# EBF6ULL_F1____AD.net
KiCad netlist of a schematic drawn in Altium Designer
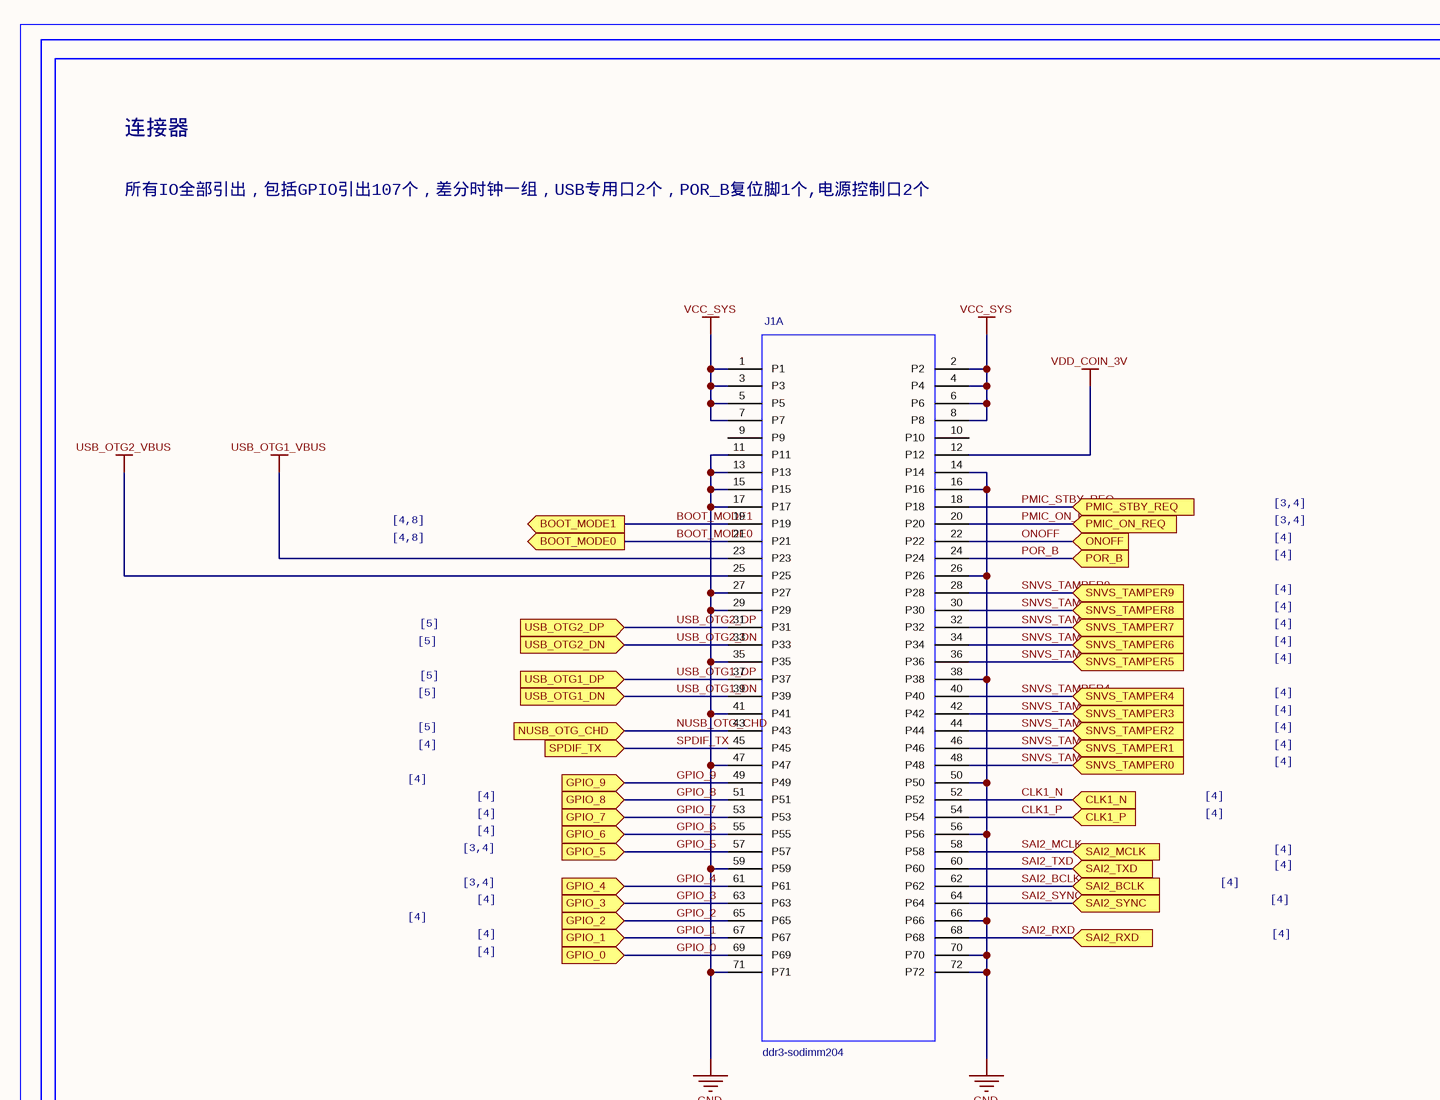
[diagram p0: 野火_EBF6ULL F1 核心板_原理图封装参考设计_AD格式.SchDoc, top left]
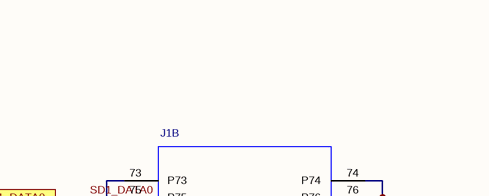
[diagram p1: 野火_EBF6ULL F1 核心板_原理图封装参考设计_AD格式.SchDoc, top right]
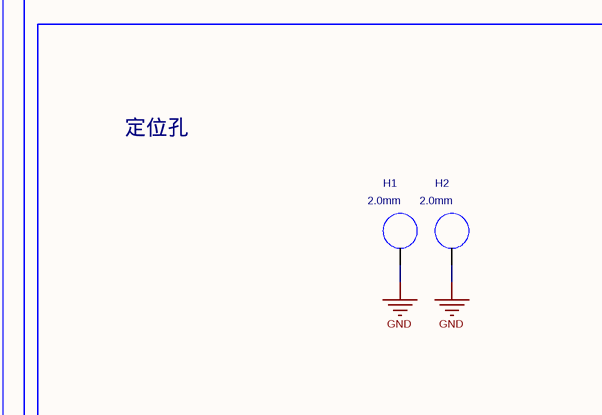
[diagram p2: 野火_EBF6ULL F1 核心板_原理图封装参考设计_AD格式.SchDoc, bottom left]
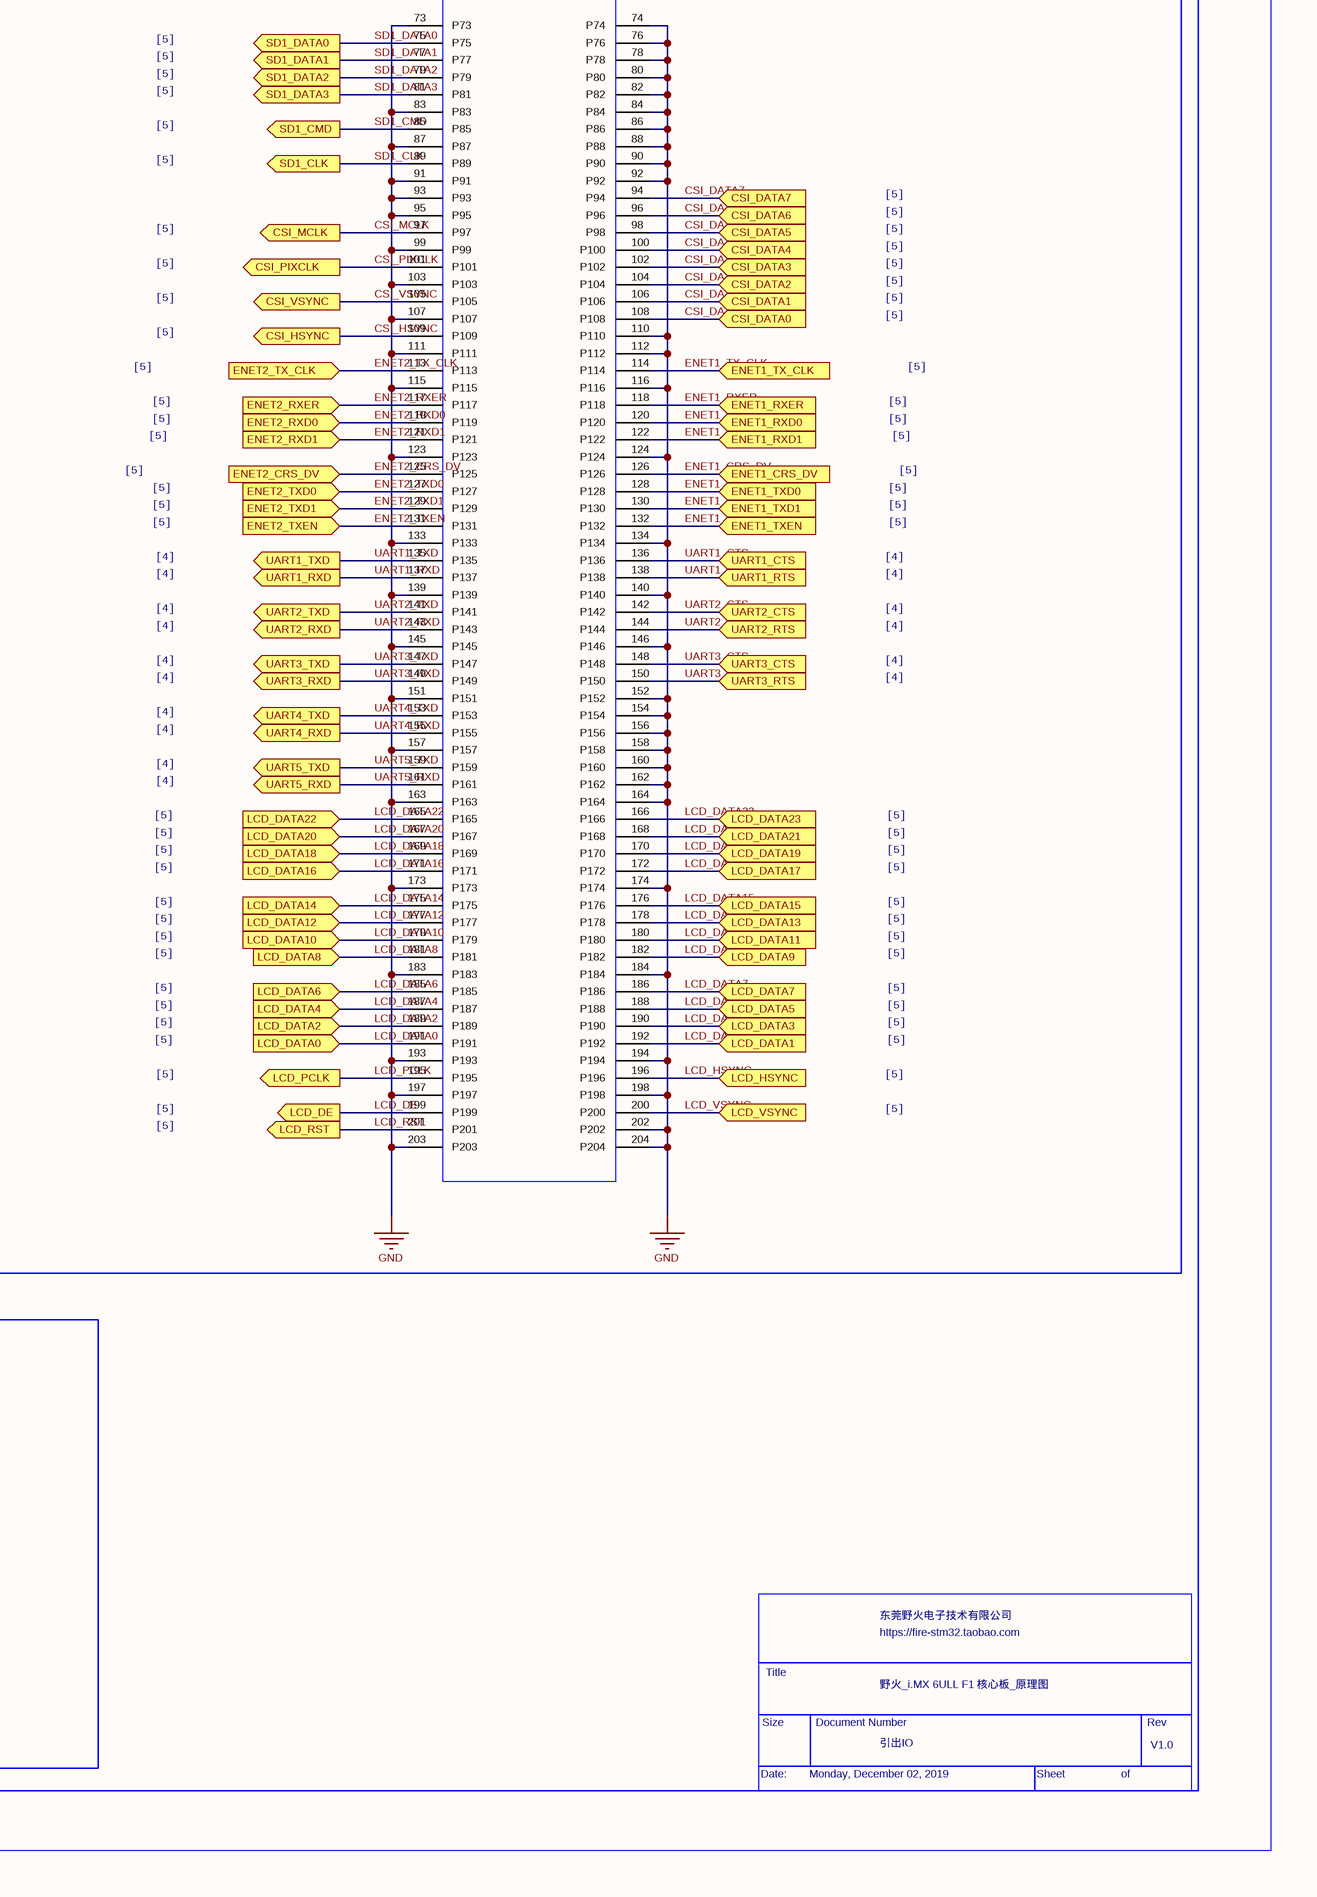
[diagram p3: 野火_EBF6ULL F1 核心板_原理图封装参考设计_AD格式.SchDoc, bottom right]

(export (version "E")
  (design (tool "Eeschema 10.0.6"))
  (components
    (comp (ref "H1")
      (value "2.0mm")
      (footprint "T2_5-4")
      (description "FASTENER, STANDOFF 4.5MMX3.53XM3.0X0.5 ROUND THR .635\"L BRASS")
      (fields (field (name "Comment") "SPACER_0"))
      (libsource (lib "*") (part "SPACER_0"))
    )
    (comp (ref "H2")
      (value "2.0mm")
      (footprint "T2_5-4")
      (description "FASTENER, STANDOFF 4.5MMX3.53XM3.0X0.5 ROUND THR .635\"L BRASS")
      (fields (field (name "Comment") "SPACER_0"))
      (libsource (lib "*") (part "SPACER_0"))
    )
    (comp (ref "J1")
      (value "ddr3-sodimm204")
      (footprint "DDR3-SODIMM204-GOLD_FINGER")
      (fields (field (name "Comment") "DDR3-SODIMM204"))
      (libsource (lib "*") (part "DDR3-SODIMM204"))
    )
  )
  (nets
    (net (code "1") (name "/BOOT_MODE0") (class "Default")
      (node (ref "J1") (pin "21") (pinfunction "P21_21") (pintype "passive"))
    )
    (net (code "2") (name "/BOOT_MODE1") (class "Default")
      (node (ref "J1") (pin "19") (pinfunction "P19_19") (pintype "passive"))
    )
    (net (code "3") (name "/CLK1_N") (class "Default")
      (node (ref "J1") (pin "52") (pinfunction "P52_52") (pintype "passive"))
    )
    (net (code "4") (name "/CLK1_P") (class "Default")
      (node (ref "J1") (pin "54") (pinfunction "P54_54") (pintype "passive"))
    )
    (net (code "5") (name "/CSI_DATA0") (class "Default")
      (node (ref "J1") (pin "108") (pinfunction "P108_108") (pintype "passive"))
    )
    (net (code "6") (name "/CSI_DATA1") (class "Default")
      (node (ref "J1") (pin "106") (pinfunction "P106_106") (pintype "passive"))
    )
    (net (code "7") (name "/CSI_DATA2") (class "Default")
      (node (ref "J1") (pin "104") (pinfunction "P104_104") (pintype "passive"))
    )
    (net (code "8") (name "/CSI_DATA3") (class "Default")
      (node (ref "J1") (pin "102") (pinfunction "P102_102") (pintype "passive"))
    )
    (net (code "9") (name "/CSI_DATA4") (class "Default")
      (node (ref "J1") (pin "100") (pinfunction "P100_100") (pintype "passive"))
    )
    (net (code "10") (name "/CSI_DATA5") (class "Default")
      (node (ref "J1") (pin "98") (pinfunction "P98_98") (pintype "passive"))
    )
    (net (code "11") (name "/CSI_DATA6") (class "Default")
      (node (ref "J1") (pin "96") (pinfunction "P96_96") (pintype "passive"))
    )
    (net (code "12") (name "/CSI_DATA7") (class "Default")
      (node (ref "J1") (pin "94") (pinfunction "P94_94") (pintype "passive"))
    )
    (net (code "13") (name "/CSI_HSYNC") (class "Default")
      (node (ref "J1") (pin "109") (pinfunction "P109_109") (pintype "passive"))
    )
    (net (code "14") (name "/CSI_MCLK") (class "Default")
      (node (ref "J1") (pin "97") (pinfunction "P97_97") (pintype "passive"))
    )
    (net (code "15") (name "/CSI_PIXCLK") (class "Default")
      (node (ref "J1") (pin "101") (pinfunction "P101_101") (pintype "passive"))
    )
    (net (code "16") (name "/CSI_VSYNC") (class "Default")
      (node (ref "J1") (pin "105") (pinfunction "P105_105") (pintype "passive"))
    )
    (net (code "17") (name "/ENET1_CRS_DV") (class "Default")
      (node (ref "J1") (pin "126") (pinfunction "P126_126") (pintype "passive"))
    )
    (net (code "18") (name "/ENET1_RXD0") (class "Default")
      (node (ref "J1") (pin "120") (pinfunction "P120_120") (pintype "passive"))
    )
    (net (code "19") (name "/ENET1_RXD1") (class "Default")
      (node (ref "J1") (pin "122") (pinfunction "P122_122") (pintype "passive"))
    )
    (net (code "20") (name "/ENET1_RXER") (class "Default")
      (node (ref "J1") (pin "118") (pinfunction "P118_118") (pintype "passive"))
    )
    (net (code "21") (name "/ENET1_TXD0") (class "Default")
      (node (ref "J1") (pin "128") (pinfunction "P128_128") (pintype "passive"))
    )
    (net (code "22") (name "/ENET1_TXD1") (class "Default")
      (node (ref "J1") (pin "130") (pinfunction "P130_130") (pintype "passive"))
    )
    (net (code "23") (name "/ENET1_TXEN") (class "Default")
      (node (ref "J1") (pin "132") (pinfunction "P132_132") (pintype "passive"))
    )
    (net (code "24") (name "/ENET1_TX_CLK") (class "Default")
      (node (ref "J1") (pin "114") (pinfunction "P114_114") (pintype "passive"))
    )
    (net (code "25") (name "/ENET2_CRS_DV") (class "Default")
      (node (ref "J1") (pin "125") (pinfunction "P125_125") (pintype "passive"))
    )
    (net (code "26") (name "/ENET2_RXD0") (class "Default")
      (node (ref "J1") (pin "119") (pinfunction "P119_119") (pintype "passive"))
    )
    (net (code "27") (name "/ENET2_RXD1") (class "Default")
      (node (ref "J1") (pin "121") (pinfunction "P121_121") (pintype "passive"))
    )
    (net (code "28") (name "/ENET2_RXER") (class "Default")
      (node (ref "J1") (pin "117") (pinfunction "P117_117") (pintype "passive"))
    )
    (net (code "29") (name "/ENET2_TXD0") (class "Default")
      (node (ref "J1") (pin "127") (pinfunction "P127_127") (pintype "passive"))
    )
    (net (code "30") (name "/ENET2_TXD1") (class "Default")
      (node (ref "J1") (pin "129") (pinfunction "P129_129") (pintype "passive"))
    )
    (net (code "31") (name "/ENET2_TXEN") (class "Default")
      (node (ref "J1") (pin "131") (pinfunction "P131_131") (pintype "passive"))
    )
    (net (code "32") (name "/ENET2_TX_CLK") (class "Default")
      (node (ref "J1") (pin "113") (pinfunction "P113_113") (pintype "passive"))
    )
    (net (code "33") (name "/GPIO_0") (class "Default")
      (node (ref "J1") (pin "69") (pinfunction "P69_69") (pintype "passive"))
    )
    (net (code "34") (name "/GPIO_1") (class "Default")
      (node (ref "J1") (pin "67") (pinfunction "P67_67") (pintype "passive"))
    )
    (net (code "35") (name "/GPIO_2") (class "Default")
      (node (ref "J1") (pin "65") (pinfunction "P65_65") (pintype "passive"))
    )
    (net (code "36") (name "/GPIO_3") (class "Default")
      (node (ref "J1") (pin "63") (pinfunction "P63_63") (pintype "passive"))
    )
    (net (code "37") (name "/GPIO_4") (class "Default")
      (node (ref "J1") (pin "61") (pinfunction "P61_61") (pintype "passive"))
    )
    (net (code "38") (name "/GPIO_5") (class "Default")
      (node (ref "J1") (pin "57") (pinfunction "P57_57") (pintype "passive"))
    )
    (net (code "39") (name "/GPIO_6") (class "Default")
      (node (ref "J1") (pin "55") (pinfunction "P55_55") (pintype "passive"))
    )
    (net (code "40") (name "/GPIO_7") (class "Default")
      (node (ref "J1") (pin "53") (pinfunction "P53_53") (pintype "passive"))
    )
    (net (code "41") (name "/GPIO_8") (class "Default")
      (node (ref "J1") (pin "51") (pinfunction "P51_51") (pintype "passive"))
    )
    (net (code "42") (name "/GPIO_9") (class "Default")
      (node (ref "J1") (pin "49") (pinfunction "P49_49") (pintype "passive"))
    )
    (net (code "43") (name "/LCD_DATA0") (class "Default")
      (node (ref "J1") (pin "191") (pinfunction "P191_191") (pintype "passive"))
    )
    (net (code "44") (name "/LCD_DATA1") (class "Default")
      (node (ref "J1") (pin "192") (pinfunction "P192_192") (pintype "passive"))
    )
    (net (code "45") (name "/LCD_DATA2") (class "Default")
      (node (ref "J1") (pin "189") (pinfunction "P189_189") (pintype "passive"))
    )
    (net (code "46") (name "/LCD_DATA3") (class "Default")
      (node (ref "J1") (pin "190") (pinfunction "P190_190") (pintype "passive"))
    )
    (net (code "47") (name "/LCD_DATA4") (class "Default")
      (node (ref "J1") (pin "187") (pinfunction "P187_187") (pintype "passive"))
    )
    (net (code "48") (name "/LCD_DATA5") (class "Default")
      (node (ref "J1") (pin "188") (pinfunction "P188_188") (pintype "passive"))
    )
    (net (code "49") (name "/LCD_DATA6") (class "Default")
      (node (ref "J1") (pin "185") (pinfunction "P185_185") (pintype "passive"))
    )
    (net (code "50") (name "/LCD_DATA7") (class "Default")
      (node (ref "J1") (pin "186") (pinfunction "P186_186") (pintype "passive"))
    )
    (net (code "51") (name "/LCD_DATA8") (class "Default")
      (node (ref "J1") (pin "181") (pinfunction "P181_181") (pintype "passive"))
    )
    (net (code "52") (name "/LCD_DATA9") (class "Default")
      (node (ref "J1") (pin "182") (pinfunction "P182_182") (pintype "passive"))
    )
    (net (code "53") (name "/LCD_DATA10") (class "Default")
      (node (ref "J1") (pin "179") (pinfunction "P179_179") (pintype "passive"))
    )
    (net (code "54") (name "/LCD_DATA11") (class "Default")
      (node (ref "J1") (pin "180") (pinfunction "P180_180") (pintype "passive"))
    )
    (net (code "55") (name "/LCD_DATA12") (class "Default")
      (node (ref "J1") (pin "177") (pinfunction "P177_177") (pintype "passive"))
    )
    (net (code "56") (name "/LCD_DATA13") (class "Default")
      (node (ref "J1") (pin "178") (pinfunction "P178_178") (pintype "passive"))
    )
    (net (code "57") (name "/LCD_DATA14") (class "Default")
      (node (ref "J1") (pin "175") (pinfunction "P175_175") (pintype "passive"))
    )
    (net (code "58") (name "/LCD_DATA15") (class "Default")
      (node (ref "J1") (pin "176") (pinfunction "P176_176") (pintype "passive"))
    )
    (net (code "59") (name "/LCD_DATA16") (class "Default")
      (node (ref "J1") (pin "171") (pinfunction "P171_171") (pintype "passive"))
    )
    (net (code "60") (name "/LCD_DATA17") (class "Default")
      (node (ref "J1") (pin "172") (pinfunction "P172_172") (pintype "passive"))
    )
    (net (code "61") (name "/LCD_DATA18") (class "Default")
      (node (ref "J1") (pin "169") (pinfunction "P169_169") (pintype "passive"))
    )
    (net (code "62") (name "/LCD_DATA19") (class "Default")
      (node (ref "J1") (pin "170") (pinfunction "P170_170") (pintype "passive"))
    )
    (net (code "63") (name "/LCD_DATA20") (class "Default")
      (node (ref "J1") (pin "167") (pinfunction "P167_167") (pintype "passive"))
    )
    (net (code "64") (name "/LCD_DATA21") (class "Default")
      (node (ref "J1") (pin "168") (pinfunction "P168_168") (pintype "passive"))
    )
    (net (code "65") (name "/LCD_DATA22") (class "Default")
      (node (ref "J1") (pin "165") (pinfunction "P165_165") (pintype "passive"))
    )
    (net (code "66") (name "/LCD_DATA23") (class "Default")
      (node (ref "J1") (pin "166") (pinfunction "P166_166") (pintype "passive"))
    )
    (net (code "67") (name "/LCD_DE") (class "Default")
      (node (ref "J1") (pin "199") (pinfunction "P199_199") (pintype "passive"))
    )
    (net (code "68") (name "/LCD_HSYNC") (class "Default")
      (node (ref "J1") (pin "196") (pinfunction "P196_196") (pintype "passive"))
    )
    (net (code "69") (name "/LCD_PCLK") (class "Default")
      (node (ref "J1") (pin "195") (pinfunction "P195_195") (pintype "passive"))
    )
    (net (code "70") (name "/LCD_RST") (class "Default")
      (node (ref "J1") (pin "201") (pinfunction "P201_201") (pintype "passive"))
    )
    (net (code "71") (name "/LCD_VSYNC") (class "Default")
      (node (ref "J1") (pin "200") (pinfunction "P200_200") (pintype "passive"))
    )
    (net (code "72") (name "/NUSB_OTG_CHD") (class "Default")
      (node (ref "J1") (pin "43") (pinfunction "P43_43") (pintype "passive"))
    )
    (net (code "73") (name "/ONOFF") (class "Default")
      (node (ref "J1") (pin "22") (pinfunction "P22_22") (pintype "passive"))
    )
    (net (code "74") (name "/PMIC_ON_REQ") (class "Default")
      (node (ref "J1") (pin "20") (pinfunction "P20_20") (pintype "passive"))
    )
    (net (code "75") (name "/PMIC_STBY_REQ") (class "Default")
      (node (ref "J1") (pin "18") (pinfunction "P18_18") (pintype "passive"))
    )
    (net (code "76") (name "/POR_B") (class "Default")
      (node (ref "J1") (pin "24") (pinfunction "P24_24") (pintype "passive"))
    )
    (net (code "77") (name "/SAI2_BCLK") (class "Default")
      (node (ref "J1") (pin "62") (pinfunction "P62_62") (pintype "passive"))
    )
    (net (code "78") (name "/SAI2_MCLK") (class "Default")
      (node (ref "J1") (pin "58") (pinfunction "P58_58") (pintype "passive"))
    )
    (net (code "79") (name "/SAI2_RXD") (class "Default")
      (node (ref "J1") (pin "68") (pinfunction "P68_68") (pintype "passive"))
    )
    (net (code "80") (name "/SAI2_SYNC") (class "Default")
      (node (ref "J1") (pin "64") (pinfunction "P64_64") (pintype "passive"))
    )
    (net (code "81") (name "/SAI2_TXD") (class "Default")
      (node (ref "J1") (pin "60") (pinfunction "P60_60") (pintype "passive"))
    )
    (net (code "82") (name "/SD1_CLK") (class "Default")
      (node (ref "J1") (pin "89") (pinfunction "P89_89") (pintype "passive"))
    )
    (net (code "83") (name "/SD1_CMD") (class "Default")
      (node (ref "J1") (pin "85") (pinfunction "P85_85") (pintype "passive"))
    )
    (net (code "84") (name "/SD1_DATA0") (class "Default")
      (node (ref "J1") (pin "75") (pinfunction "P75_75") (pintype "passive"))
    )
    (net (code "85") (name "/SD1_DATA1") (class "Default")
      (node (ref "J1") (pin "77") (pinfunction "P77_77") (pintype "passive"))
    )
    (net (code "86") (name "/SD1_DATA2") (class "Default")
      (node (ref "J1") (pin "79") (pinfunction "P79_79") (pintype "passive"))
    )
    (net (code "87") (name "/SD1_DATA3") (class "Default")
      (node (ref "J1") (pin "81") (pinfunction "P81_81") (pintype "passive"))
    )
    (net (code "88") (name "/SNVS_TAMPER0") (class "Default")
      (node (ref "J1") (pin "48") (pinfunction "P48_48") (pintype "passive"))
    )
    (net (code "89") (name "/SNVS_TAMPER1") (class "Default")
      (node (ref "J1") (pin "46") (pinfunction "P46_46") (pintype "passive"))
    )
    (net (code "90") (name "/SNVS_TAMPER2") (class "Default")
      (node (ref "J1") (pin "44") (pinfunction "P44_44") (pintype "passive"))
    )
    (net (code "91") (name "/SNVS_TAMPER3") (class "Default")
      (node (ref "J1") (pin "42") (pinfunction "P42_42") (pintype "passive"))
    )
    (net (code "92") (name "/SNVS_TAMPER4") (class "Default")
      (node (ref "J1") (pin "40") (pinfunction "P40_40") (pintype "passive"))
    )
    (net (code "93") (name "/SNVS_TAMPER5") (class "Default")
      (node (ref "J1") (pin "36") (pinfunction "P36_36") (pintype "passive"))
    )
    (net (code "94") (name "/SNVS_TAMPER6") (class "Default")
      (node (ref "J1") (pin "34") (pinfunction "P34_34") (pintype "passive"))
    )
    (net (code "95") (name "/SNVS_TAMPER7") (class "Default")
      (node (ref "J1") (pin "32") (pinfunction "P32_32") (pintype "passive"))
    )
    (net (code "96") (name "/SNVS_TAMPER8") (class "Default")
      (node (ref "J1") (pin "30") (pinfunction "P30_30") (pintype "passive"))
    )
    (net (code "97") (name "/SNVS_TAMPER9") (class "Default")
      (node (ref "J1") (pin "28") (pinfunction "P28_28") (pintype "passive"))
    )
    (net (code "98") (name "/SPDIF_TX") (class "Default")
      (node (ref "J1") (pin "45") (pinfunction "P45_45") (pintype "passive"))
    )
    (net (code "99") (name "/UART1_CTS") (class "Default")
      (node (ref "J1") (pin "136") (pinfunction "P136_136") (pintype "passive"))
    )
    (net (code "100") (name "/UART1_RTS") (class "Default")
      (node (ref "J1") (pin "138") (pinfunction "P138_138") (pintype "passive"))
    )
    (net (code "101") (name "/UART1_RXD") (class "Default")
      (node (ref "J1") (pin "137") (pinfunction "P137_137") (pintype "passive"))
    )
    (net (code "102") (name "/UART1_TXD") (class "Default")
      (node (ref "J1") (pin "135") (pinfunction "P135_135") (pintype "passive"))
    )
    (net (code "103") (name "/UART2_CTS") (class "Default")
      (node (ref "J1") (pin "142") (pinfunction "P142_142") (pintype "passive"))
    )
    (net (code "104") (name "/UART2_RTS") (class "Default")
      (node (ref "J1") (pin "144") (pinfunction "P144_144") (pintype "passive"))
    )
    (net (code "105") (name "/UART2_RXD") (class "Default")
      (node (ref "J1") (pin "143") (pinfunction "P143_143") (pintype "passive"))
    )
    (net (code "106") (name "/UART2_TXD") (class "Default")
      (node (ref "J1") (pin "141") (pinfunction "P141_141") (pintype "passive"))
    )
    (net (code "107") (name "/UART3_CTS") (class "Default")
      (node (ref "J1") (pin "148") (pinfunction "P148_148") (pintype "passive"))
    )
    (net (code "108") (name "/UART3_RTS") (class "Default")
      (node (ref "J1") (pin "150") (pinfunction "P150_150") (pintype "passive"))
    )
    (net (code "109") (name "/UART3_RXD") (class "Default")
      (node (ref "J1") (pin "149") (pinfunction "P149_149") (pintype "passive"))
    )
    (net (code "110") (name "/UART3_TXD") (class "Default")
      (node (ref "J1") (pin "147") (pinfunction "P147_147") (pintype "passive"))
    )
    (net (code "111") (name "/UART4_RXD") (class "Default")
      (node (ref "J1") (pin "155") (pinfunction "P155_155") (pintype "passive"))
    )
    (net (code "112") (name "/UART4_TXD") (class "Default")
      (node (ref "J1") (pin "153") (pinfunction "P153_153") (pintype "passive"))
    )
    (net (code "113") (name "/UART5_RXD") (class "Default")
      (node (ref "J1") (pin "161") (pinfunction "P161_161") (pintype "passive"))
    )
    (net (code "114") (name "/UART5_TXD") (class "Default")
      (node (ref "J1") (pin "159") (pinfunction "P159_159") (pintype "passive"))
    )
    (net (code "115") (name "/USB_OTG1_DN") (class "Default")
      (node (ref "J1") (pin "39") (pinfunction "P39_39") (pintype "passive"))
    )
    (net (code "116") (name "/USB_OTG1_DP") (class "Default")
      (node (ref "J1") (pin "37") (pinfunction "P37_37") (pintype "passive"))
    )
    (net (code "117") (name "/USB_OTG2_DN") (class "Default")
      (node (ref "J1") (pin "33") (pinfunction "P33_33") (pintype "passive"))
    )
    (net (code "118") (name "/USB_OTG2_DP") (class "Default")
      (node (ref "J1") (pin "31") (pinfunction "P31_31") (pintype "passive"))
    )
    (net (code "119") (name "GND") (class "Default")
      (node (ref "H1") (pin "1") (pinfunction "NC_1_1") (pintype "passive"))
      (node (ref "H2") (pin "1") (pinfunction "NC_1_1") (pintype "passive"))
      (node (ref "J1") (pin "103") (pinfunction "P103_103") (pintype "passive"))
      (node (ref "J1") (pin "107") (pinfunction "P107_107") (pintype "passive"))
      (node (ref "J1") (pin "11") (pinfunction "P11_11") (pintype "passive"))
      (node (ref "J1") (pin "110") (pinfunction "P110_110") (pintype "passive"))
      (node (ref "J1") (pin "111") (pinfunction "P111_111") (pintype "passive"))
      (node (ref "J1") (pin "112") (pinfunction "P112_112") (pintype "passive"))
      (node (ref "J1") (pin "115") (pinfunction "P115_115") (pintype "passive"))
      (node (ref "J1") (pin "116") (pinfunction "P116_116") (pintype "passive"))
      (node (ref "J1") (pin "123") (pinfunction "P123_123") (pintype "passive"))
      (node (ref "J1") (pin "124") (pinfunction "P124_124") (pintype "passive"))
      (node (ref "J1") (pin "13") (pinfunction "P13_13") (pintype "passive"))
      (node (ref "J1") (pin "133") (pinfunction "P133_133") (pintype "passive"))
      (node (ref "J1") (pin "134") (pinfunction "P134_134") (pintype "passive"))
      (node (ref "J1") (pin "139") (pinfunction "P139_139") (pintype "passive"))
      (node (ref "J1") (pin "14") (pinfunction "P14_14") (pintype "passive"))
      (node (ref "J1") (pin "140") (pinfunction "P140_140") (pintype "passive"))
      (node (ref "J1") (pin "145") (pinfunction "P145_145") (pintype "passive"))
      (node (ref "J1") (pin "146") (pinfunction "P146_146") (pintype "passive"))
      (node (ref "J1") (pin "15") (pinfunction "P15_15") (pintype "passive"))
      (node (ref "J1") (pin "151") (pinfunction "P151_151") (pintype "passive"))
      (node (ref "J1") (pin "152") (pinfunction "P152_152") (pintype "passive"))
      (node (ref "J1") (pin "154") (pinfunction "P154_154") (pintype "passive"))
      (node (ref "J1") (pin "156") (pinfunction "P156_156") (pintype "passive"))
      (node (ref "J1") (pin "157") (pinfunction "P157_157") (pintype "passive"))
      (node (ref "J1") (pin "158") (pinfunction "P158_158") (pintype "passive"))
      (node (ref "J1") (pin "16") (pinfunction "P16_16") (pintype "passive"))
      (node (ref "J1") (pin "160") (pinfunction "P160_160") (pintype "passive"))
      (node (ref "J1") (pin "162") (pinfunction "P162_162") (pintype "passive"))
      (node (ref "J1") (pin "163") (pinfunction "P163_163") (pintype "passive"))
      (node (ref "J1") (pin "164") (pinfunction "P164_164") (pintype "passive"))
      (node (ref "J1") (pin "17") (pinfunction "P17_17") (pintype "passive"))
      (node (ref "J1") (pin "173") (pinfunction "P173_173") (pintype "passive"))
      (node (ref "J1") (pin "174") (pinfunction "P174_174") (pintype "passive"))
      (node (ref "J1") (pin "183") (pinfunction "P183_183") (pintype "passive"))
      (node (ref "J1") (pin "184") (pinfunction "P184_184") (pintype "passive"))
      (node (ref "J1") (pin "193") (pinfunction "P193_193") (pintype "passive"))
      (node (ref "J1") (pin "194") (pinfunction "P194_194") (pintype "passive"))
      (node (ref "J1") (pin "197") (pinfunction "P197_197") (pintype "passive"))
      (node (ref "J1") (pin "198") (pinfunction "P198_198") (pintype "passive"))
      (node (ref "J1") (pin "202") (pinfunction "P202_202") (pintype "passive"))
      (node (ref "J1") (pin "203") (pinfunction "P203_203") (pintype "passive"))
      (node (ref "J1") (pin "204") (pinfunction "P204_204") (pintype "passive"))
      (node (ref "J1") (pin "26") (pinfunction "P26_26") (pintype "passive"))
      (node (ref "J1") (pin "27") (pinfunction "P27_27") (pintype "passive"))
      (node (ref "J1") (pin "29") (pinfunction "P29_29") (pintype "passive"))
      (node (ref "J1") (pin "35") (pinfunction "P35_35") (pintype "passive"))
      (node (ref "J1") (pin "38") (pinfunction "P38_38") (pintype "passive"))
      (node (ref "J1") (pin "41") (pinfunction "P41_41") (pintype "passive"))
      (node (ref "J1") (pin "47") (pinfunction "P47_47") (pintype "passive"))
      (node (ref "J1") (pin "50") (pinfunction "P50_50") (pintype "passive"))
      (node (ref "J1") (pin "56") (pinfunction "P56_56") (pintype "passive"))
      (node (ref "J1") (pin "59") (pinfunction "P59_59") (pintype "passive"))
      (node (ref "J1") (pin "66") (pinfunction "P66_66") (pintype "passive"))
      (node (ref "J1") (pin "70") (pinfunction "P70_70") (pintype "passive"))
      (node (ref "J1") (pin "71") (pinfunction "P71_71") (pintype "passive"))
      (node (ref "J1") (pin "72") (pinfunction "P72_72") (pintype "passive"))
      (node (ref "J1") (pin "73") (pinfunction "P73_73") (pintype "passive"))
      (node (ref "J1") (pin "74") (pinfunction "P74_74") (pintype "passive"))
      (node (ref "J1") (pin "76") (pinfunction "P76_76") (pintype "passive"))
      (node (ref "J1") (pin "78") (pinfunction "P78_78") (pintype "passive"))
      (node (ref "J1") (pin "80") (pinfunction "P80_80") (pintype "passive"))
      (node (ref "J1") (pin "82") (pinfunction "P82_82") (pintype "passive"))
      (node (ref "J1") (pin "83") (pinfunction "P83_83") (pintype "passive"))
      (node (ref "J1") (pin "84") (pinfunction "P84_84") (pintype "passive"))
      (node (ref "J1") (pin "86") (pinfunction "P86_86") (pintype "passive"))
      (node (ref "J1") (pin "87") (pinfunction "P87_87") (pintype "passive"))
      (node (ref "J1") (pin "88") (pinfunction "P88_88") (pintype "passive"))
      (node (ref "J1") (pin "90") (pinfunction "P90_90") (pintype "passive"))
      (node (ref "J1") (pin "91") (pinfunction "P91_91") (pintype "passive"))
      (node (ref "J1") (pin "92") (pinfunction "P92_92") (pintype "passive"))
      (node (ref "J1") (pin "93") (pinfunction "P93_93") (pintype "passive"))
      (node (ref "J1") (pin "95") (pinfunction "P95_95") (pintype "passive"))
      (node (ref "J1") (pin "99") (pinfunction "P99_99") (pintype "passive"))
    )
    (net (code "120") (name "USB_OTG1_VBUS") (class "Default")
      (node (ref "J1") (pin "23") (pinfunction "P23_23") (pintype "passive"))
    )
    (net (code "121") (name "USB_OTG2_VBUS") (class "Default")
      (node (ref "J1") (pin "25") (pinfunction "P25_25") (pintype "passive"))
    )
    (net (code "122") (name "VCC_SYS") (class "Default")
      (node (ref "J1") (pin "1") (pinfunction "P1_1") (pintype "passive"))
      (node (ref "J1") (pin "2") (pinfunction "P2_2") (pintype "passive"))
      (node (ref "J1") (pin "3") (pinfunction "P3_3") (pintype "passive"))
      (node (ref "J1") (pin "4") (pinfunction "P4_4") (pintype "passive"))
      (node (ref "J1") (pin "5") (pinfunction "P5_5") (pintype "passive"))
      (node (ref "J1") (pin "6") (pinfunction "P6_6") (pintype "passive"))
      (node (ref "J1") (pin "7") (pinfunction "P7_7") (pintype "passive"))
      (node (ref "J1") (pin "8") (pinfunction "P8_8") (pintype "passive"))
    )
    (net (code "123") (name "VDD_COIN_3V") (class "Default")
      (node (ref "J1") (pin "12") (pinfunction "P12_12") (pintype "passive"))
    )
    (net (code "124") (name "unconnected-(J1A-P9-Pad9)") (class "Default")
      (node (ref "J1") (pin "9") (pinfunction "P9_9") (pintype "passive"))
    )
    (net (code "125") (name "unconnected-(J1A-P10-Pad10)") (class "Default")
      (node (ref "J1") (pin "10") (pinfunction "P10_10") (pintype "passive"))
    )
  )
)
